# EPS_RBL.net
KiCad netlist of a schematic drawn in Altium Designer
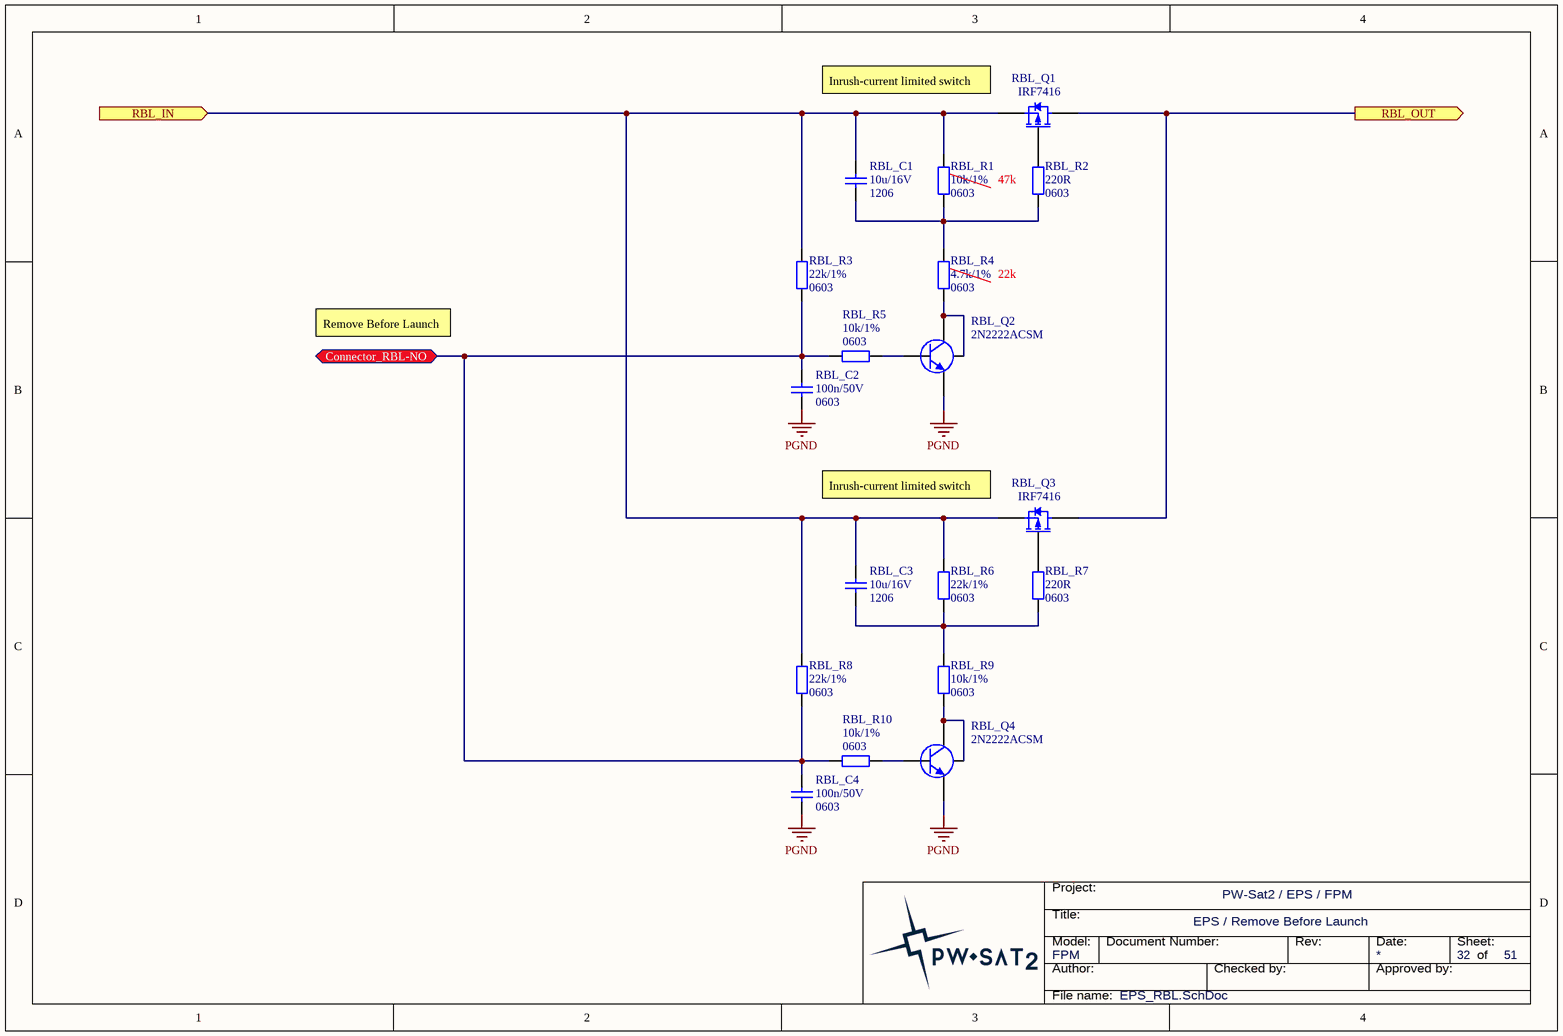
[diagram p0: EPS_RBL.SchDoc]

(export (version "E")
  (design (tool "Eeschema 10.0.6"))
  (components
    (comp (ref "RBL_C1")
      (value "10u/16V")
      (footprint "SMD_Capacitor_1206")
      (description "Ceramic Cap Kemet COTS 10u/16V X7R 1206")
      (fields
        (field (name "MANUFACTURERPARTNUMBER") "C1206T106K4RACTU")
        (field (name "MANUFACTURER") "Kemet")
        (field (name "PACKGE") "1206")
      )
      (libsource (lib "capacitors") (part "Cer_C1206T106K4RACTU"))
    )
    (comp (ref "RBL_C2")
      (value "100n/50V")
      (footprint "SMD_Capacitor_0603")
      (description "Ceramic Cap Murata Automotive 100n/50V X7R 0603")
      (fields
        (field (name "MANUFACTURER") "Murata")
        (field (name "MANUFACTURERPARTNUMBER") "GCJ188R71H104KA12D")
        (field (name "PACKAGE") "0603")
      )
      (libsource (lib "capacitors") (part "Cer_GCJ188R71H104KA12D"))
    )
    (comp (ref "RBL_C3")
      (value "10u/16V")
      (footprint "SMD_Capacitor_1206")
      (description "Ceramic Cap Kemet COTS 10u/16V X7R 1206")
      (fields
        (field (name "MANUFACTURERPARTNUMBER") "C1206T106K4RACTU")
        (field (name "MANUFACTURER") "Kemet")
        (field (name "PACKGE") "1206")
      )
      (libsource (lib "capacitors") (part "Cer_C1206T106K4RACTU"))
    )
    (comp (ref "RBL_C4")
      (value "100n/50V")
      (footprint "SMD_Capacitor_0603")
      (description "Ceramic Cap Murata Automotive 100n/50V X7R 0603")
      (fields
        (field (name "MANUFACTURER") "Murata")
        (field (name "MANUFACTURERPARTNUMBER") "GCJ188R71H104KA12D")
        (field (name "PACKAGE") "0603")
      )
      (libsource (lib "capacitors") (part "Cer_GCJ188R71H104KA12D"))
    )
    (comp (ref "RBL_Q1")
      (value "IRF7416")
      (footprint "SOIC-8-N_SSSGDDDD")
      (description "10A/30V HEXFET Power P-MOSFET.")
      (fields (field (name "MANUFACTURER") "International Rectifier"))
      (libsource (lib "transistors") (part "IRF7416"))
    )
    (comp (ref "RBL_Q2")
      (value "2N2222ACSM")
      (footprint "LCC1-4_BEC")
      (description "Silicon Planar Epitaxial NPN Transistor.")
      (fields (field (name "MANUFACTURER") "Semelab-TT"))
      (libsource (lib "transistors") (part "2N2222ACSM"))
    )
    (comp (ref "RBL_Q3")
      (value "IRF7416")
      (footprint "SOIC-8-N_SSSGDDDD")
      (description "10A/30V HEXFET Power P-MOSFET.")
      (fields (field (name "MANUFACTURER") "International Rectifier"))
      (libsource (lib "transistors") (part "IRF7416"))
    )
    (comp (ref "RBL_Q4")
      (value "2N2222ACSM")
      (footprint "LCC1-4_BEC")
      (description "Silicon Planar Epitaxial NPN Transistor.")
      (fields (field (name "MANUFACTURER") "Semelab-TT"))
      (libsource (lib "transistors") (part "2N2222ACSM"))
    )
    (comp (ref "RBL_R1")
      (value "10k/1%")
      (footprint "SMD_Resistor_0603")
      (fields (field (name "PACKAGE") "0603"))
      (libsource (lib "resistors") (part "Res"))
    )
    (comp (ref "RBL_R2")
      (value "220R")
      (footprint "SMD_Resistor_0603")
      (fields (field (name "PACKAGE") "0603"))
      (libsource (lib "resistors") (part "Res"))
    )
    (comp (ref "RBL_R3")
      (value "22k/1%")
      (footprint "SMD_Resistor_0603")
      (fields (field (name "PACKAGE") "0603"))
      (libsource (lib "resistors") (part "Res"))
    )
    (comp (ref "RBL_R4")
      (value "4.7k/1%")
      (footprint "SMD_Resistor_0603")
      (fields (field (name "PACKAGE") "0603"))
      (libsource (lib "resistors") (part "Res"))
    )
    (comp (ref "RBL_R5")
      (value "10k/1%")
      (footprint "SMD_Resistor_0603")
      (fields (field (name "PACKAGE") "0603"))
      (libsource (lib "") (part "Res_1"))
    )
    (comp (ref "RBL_R6")
      (value "22k/1%")
      (footprint "SMD_Resistor_0603")
      (fields (field (name "PACKAGE") "0603"))
      (libsource (lib "resistors") (part "Res"))
    )
    (comp (ref "RBL_R7")
      (value "220R")
      (footprint "SMD_Resistor_0603")
      (fields (field (name "PACKAGE") "0603"))
      (libsource (lib "resistors") (part "Res"))
    )
    (comp (ref "RBL_R8")
      (value "22k/1%")
      (footprint "SMD_Resistor_0603")
      (fields (field (name "PACKAGE") "0603"))
      (libsource (lib "resistors") (part "Res"))
    )
    (comp (ref "RBL_R9")
      (value "10k/1%")
      (footprint "SMD_Resistor_0603")
      (fields (field (name "PACKAGE") "0603"))
      (libsource (lib "resistors") (part "Res"))
    )
    (comp (ref "RBL_R10")
      (value "10k/1%")
      (footprint "SMD_Resistor_0603")
      (fields (field (name "PACKAGE") "0603"))
      (libsource (lib "") (part "Res_1"))
    )
  )
  (nets
    (net (code "1") (name "/Connector_RBL-NO") (class "Default")
      (node (ref "RBL_C2") (pin "1") (pinfunction "1_1") (pintype "passive"))
      (node (ref "RBL_C4") (pin "1") (pinfunction "1_1") (pintype "passive"))
      (node (ref "RBL_R10") (pin "1") (pinfunction "1_1") (pintype "passive"))
      (node (ref "RBL_R3") (pin "2") (pinfunction "2_2") (pintype "passive"))
      (node (ref "RBL_R5") (pin "1") (pinfunction "1_1") (pintype "passive"))
      (node (ref "RBL_R8") (pin "2") (pinfunction "2_2") (pintype "passive"))
    )
    (net (code "2") (name "/RBL_IN") (class "Default")
      (node (ref "RBL_C1") (pin "1") (pinfunction "1_1") (pintype "passive"))
      (node (ref "RBL_C3") (pin "1") (pinfunction "1_1") (pintype "passive"))
      (node (ref "RBL_Q1") (pin "S") (pinfunction "S_S") (pintype "passive"))
      (node (ref "RBL_Q3") (pin "S") (pinfunction "S_S") (pintype "passive"))
      (node (ref "RBL_R1") (pin "1") (pinfunction "1_1") (pintype "passive"))
      (node (ref "RBL_R3") (pin "1") (pinfunction "1_1") (pintype "passive"))
      (node (ref "RBL_R6") (pin "1") (pinfunction "1_1") (pintype "passive"))
      (node (ref "RBL_R8") (pin "1") (pinfunction "1_1") (pintype "passive"))
    )
    (net (code "3") (name "/RBL_OUT") (class "Default")
      (node (ref "RBL_Q1") (pin "D") (pinfunction "D_D") (pintype "passive"))
      (node (ref "RBL_Q3") (pin "D") (pinfunction "D_D") (pintype "passive"))
    )
    (net (code "4") (name "Net-(RBL_C1-Pad2)") (class "Default")
      (node (ref "RBL_C1") (pin "2") (pinfunction "2_2") (pintype "passive"))
      (node (ref "RBL_R1") (pin "2") (pinfunction "2_2") (pintype "passive"))
      (node (ref "RBL_R2") (pin "2") (pinfunction "2_2") (pintype "passive"))
      (node (ref "RBL_R4") (pin "1") (pinfunction "1_1") (pintype "passive"))
    )
    (net (code "5") (name "Net-(RBL_C3-Pad2)") (class "Default")
      (node (ref "RBL_C3") (pin "2") (pinfunction "2_2") (pintype "passive"))
      (node (ref "RBL_R6") (pin "2") (pinfunction "2_2") (pintype "passive"))
      (node (ref "RBL_R7") (pin "2") (pinfunction "2_2") (pintype "passive"))
      (node (ref "RBL_R9") (pin "1") (pinfunction "1_1") (pintype "passive"))
    )
    (net (code "6") (name "Net-(RBL_Q1-PadG)") (class "Default")
      (node (ref "RBL_Q1") (pin "G") (pinfunction "G_G") (pintype "passive"))
      (node (ref "RBL_R2") (pin "1") (pinfunction "1_1") (pintype "passive"))
    )
    (net (code "7") (name "Net-(RBL_Q2-PadB)") (class "Default")
      (node (ref "RBL_Q2") (pin "B") (pinfunction "B_B") (pintype "passive"))
      (node (ref "RBL_R5") (pin "2") (pinfunction "2_2") (pintype "passive"))
    )
    (net (code "8") (name "Net-(RBL_Q2-PadC)") (class "Default")
      (node (ref "RBL_Q2") (pin "C") (pinfunction "C_C") (pintype "passive"))
      (node (ref "RBL_Q2") (pin "Shield") (pinfunction "Shield_Shield") (pintype "passive"))
      (node (ref "RBL_R4") (pin "2") (pinfunction "2_2") (pintype "passive"))
    )
    (net (code "9") (name "Net-(RBL_Q3-PadG)") (class "Default")
      (node (ref "RBL_Q3") (pin "G") (pinfunction "G_G") (pintype "passive"))
      (node (ref "RBL_R7") (pin "1") (pinfunction "1_1") (pintype "passive"))
    )
    (net (code "10") (name "Net-(RBL_Q4-PadB)") (class "Default")
      (node (ref "RBL_Q4") (pin "B") (pinfunction "B_B") (pintype "passive"))
      (node (ref "RBL_R10") (pin "2") (pinfunction "2_2") (pintype "passive"))
    )
    (net (code "11") (name "Net-(RBL_Q4-PadC)") (class "Default")
      (node (ref "RBL_Q4") (pin "C") (pinfunction "C_C") (pintype "passive"))
      (node (ref "RBL_Q4") (pin "Shield") (pinfunction "Shield_Shield") (pintype "passive"))
      (node (ref "RBL_R9") (pin "2") (pinfunction "2_2") (pintype "passive"))
    )
    (net (code "12") (name "PGND") (class "Default")
      (node (ref "RBL_C2") (pin "2") (pinfunction "2_2") (pintype "passive"))
      (node (ref "RBL_C4") (pin "2") (pinfunction "2_2") (pintype "passive"))
      (node (ref "RBL_Q2") (pin "E") (pinfunction "E_E") (pintype "passive"))
      (node (ref "RBL_Q4") (pin "E") (pinfunction "E_E") (pintype "passive"))
    )
  )
)
